# driver.net
KiCad netlist of a schematic drawn in Altium Designer
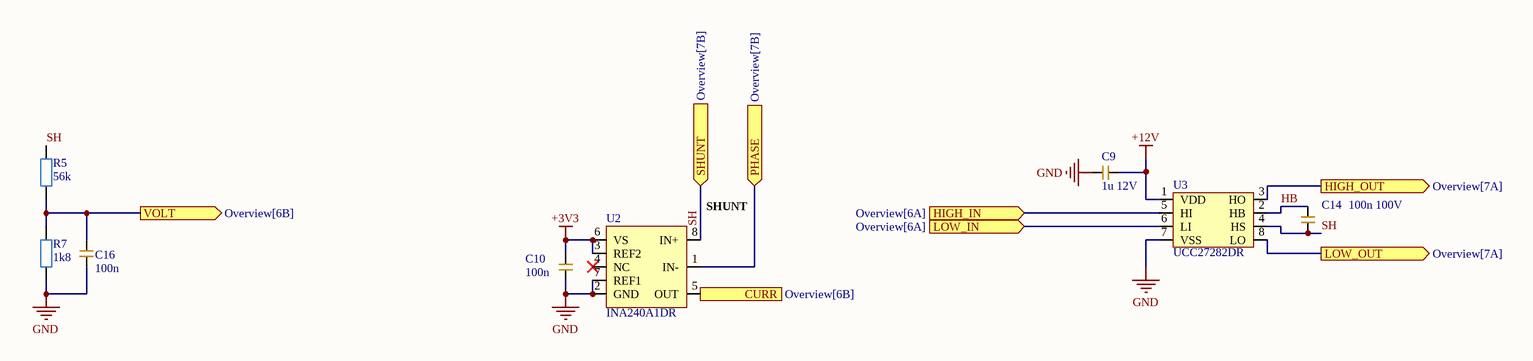
[diagram p0: driver.SchDoc]

(export (version "E")
  (design (tool "Eeschema 10.0.6"))
  (components
    (comp (ref "C9")
      (value "1u 12V")
      (footprint "CAP_0603")
      (description "Multilayer Ceramic Capacitors MLCC - SMD/SMT ROHS")
      (libsource (lib "Passive") (part "CAP_0603"))
    )
    (comp (ref "C10")
      (value "100n")
      (footprint "CAP_0603")
      (description "Multilayer Ceramic Capacitors MLCC - SMD/SMT ROHS")
      (libsource (lib "Passive") (part "CAP_0603"))
    )
    (comp (ref "C14")
      (value "100n 100V")
      (footprint "CAP_0603")
      (description "Multilayer Ceramic Capacitors MLCC - SMD/SMT ROHS")
      (libsource (lib "Passive") (part "CAP_0603"))
    )
    (comp (ref "C16")
      (value "100n")
      (footprint "CAP_0603")
      (description "Multilayer Ceramic Capacitors MLCC - SMD/SMT ROHS")
      (libsource (lib "Passive") (part "CAP_0603"))
    )
    (comp (ref "R5")
      (value "56k")
      (footprint "RES_0603")
      (description "100mW Thick Film Resistors")
      (libsource (lib "Passive") (part "RES_0603"))
    )
    (comp (ref "R7")
      (value "1k8")
      (footprint "RES_0603")
      (description "100mW Thick Film Resistors")
      (libsource (lib "Passive") (part "RES_0603"))
    )
    (comp (ref "U2")
      (value "INA240A1DR")
      (footprint "INA240A1DR")
      (description "-4V~80V Single channel SOIC-8 Current Sense Amplifiers ROHS")
      (fields (field (name "MFR.") "Texas Instruments"))
      (libsource (lib "ICs") (part "INA240A1DR"))
    )
    (comp (ref "U3")
      (value "UCC27282DR")
      (footprint "UCC27282DR")
      (description "Half Bridge 2 MOSFET 2.5A 12ns 10ns 5.5V~16V 3.5A SOIC-8 Gate Drivers ROHS")
      (fields (field (name "MFR.") "Texas Instruments"))
      (libsource (lib "ICs") (part "UCC27282DR"))
    )
  )
  (nets
    (net (code "1") (name "+3V3") (class "Default")
      (node (ref "C10") (pin "2") (pintype "passive"))
      (node (ref "U2") (pin "3") (pinfunction "REF2_3") (pintype "passive"))
      (node (ref "U2") (pin "6") (pinfunction "VS_6") (pintype "passive"))
    )
    (net (code "2") (name "+12V") (class "Default")
      (node (ref "C9") (pin "1") (pintype "passive"))
      (node (ref "U3") (pin "1") (pinfunction "VDD_1") (pintype "passive"))
    )
    (net (code "3") (name "/CURR") (class "Default")
      (node (ref "U2") (pin "5") (pinfunction "OUT_5") (pintype "passive"))
    )
    (net (code "4") (name "/HB") (class "Default")
      (node (ref "C14") (pin "2") (pintype "passive"))
      (node (ref "U3") (pin "2") (pinfunction "HB_2") (pintype "passive"))
    )
    (net (code "5") (name "/HIGH_IN") (class "Default")
      (node (ref "U3") (pin "5") (pinfunction "HI_5") (pintype "passive"))
    )
    (net (code "6") (name "/HIGH_OUT") (class "Default")
      (node (ref "U3") (pin "3") (pinfunction "HO_3") (pintype "passive"))
    )
    (net (code "7") (name "/LOW_IN") (class "Default")
      (node (ref "U3") (pin "6") (pinfunction "LI_6") (pintype "passive"))
    )
    (net (code "8") (name "/LOW_OUT") (class "Default")
      (node (ref "U3") (pin "8") (pinfunction "LO_8") (pintype "passive"))
    )
    (net (code "9") (name "/PHASE") (class "Default")
      (node (ref "U2") (pin "1") (pinfunction "IN-_1") (pintype "passive"))
    )
    (net (code "10") (name "/SH") (class "Default")
      (node (ref "C14") (pin "1") (pintype "passive"))
      (node (ref "R5") (pin "2") (pintype "passive"))
      (node (ref "U2") (pin "8") (pinfunction "IN+_8") (pintype "passive"))
      (node (ref "U3") (pin "4") (pinfunction "HS_4") (pintype "passive"))
    )
    (net (code "11") (name "/VOLT") (class "Default")
      (node (ref "C16") (pin "2") (pintype "passive"))
      (node (ref "R5") (pin "1") (pintype "passive"))
      (node (ref "R7") (pin "2") (pintype "passive"))
    )
    (net (code "12") (name "GND") (class "Default")
      (node (ref "C10") (pin "1") (pintype "passive"))
      (node (ref "C16") (pin "1") (pintype "passive"))
      (node (ref "C9") (pin "2") (pintype "passive"))
      (node (ref "R7") (pin "1") (pintype "passive"))
      (node (ref "U2") (pin "2") (pinfunction "GND_2") (pintype "passive"))
      (node (ref "U2") (pin "7") (pinfunction "REF1_7") (pintype "passive"))
      (node (ref "U3") (pin "7") (pinfunction "VSS_7") (pintype "passive"))
    )
    (net (code "13") (name "unconnected-(U2-NC-Pad4)") (class "Default")
      (node (ref "U2") (pin "4") (pinfunction "NC_4") (pintype "passive+no_connect"))
    )
  )
)
